# turntable.net
KiCad netlist of a schematic drawn in EAGLE
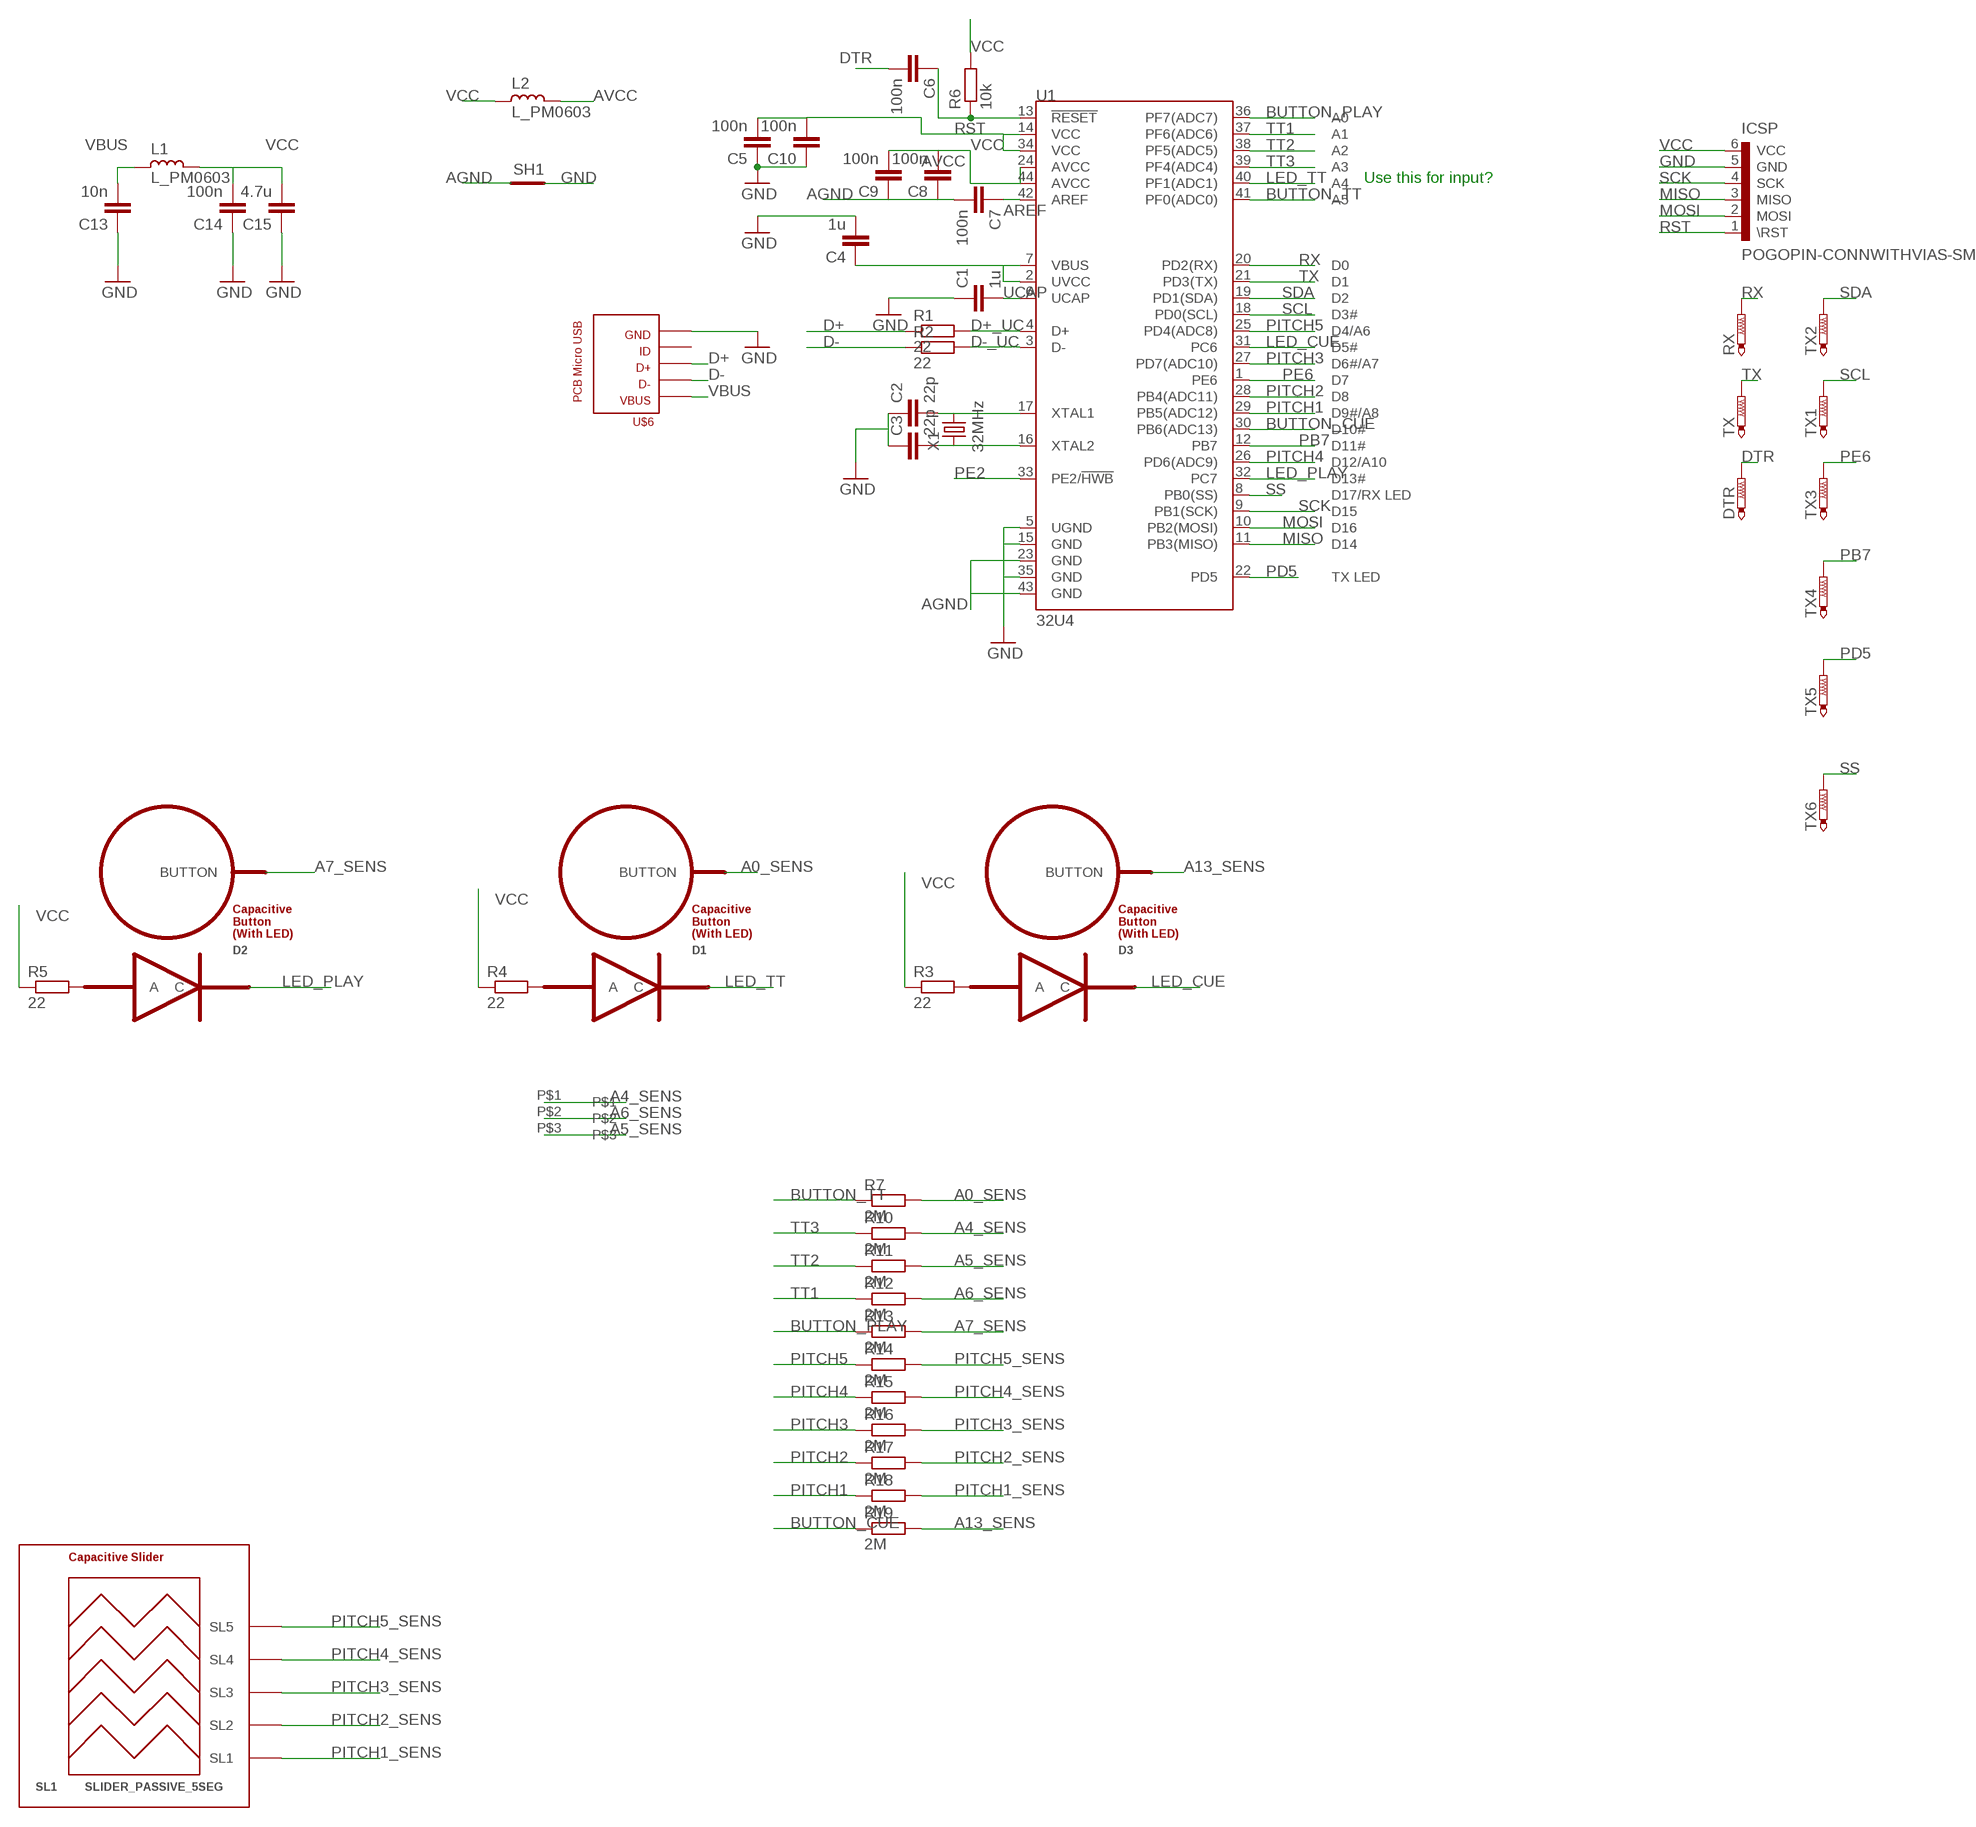
[diagram p0: schematic, sheet 1]

(export (version "E")
  (design (tool "Eeschema 10.0.6"))
  (components
    (comp (ref "C1")
      (value "1u")
      (footprint "eagle-import:C0402")
      (libsource (lib "eagle-import") (part "C-EUC0402"))
    )
    (comp (ref "C2")
      (value "22p")
      (footprint "eagle-import:C0402")
      (libsource (lib "eagle-import") (part "C-EUC0402"))
    )
    (comp (ref "C3")
      (value "22p")
      (footprint "eagle-import:C0402")
      (libsource (lib "eagle-import") (part "C-EUC0402"))
    )
    (comp (ref "C4")
      (value "1u")
      (footprint "eagle-import:C0402")
      (libsource (lib "eagle-import") (part "C-EUC0402"))
    )
    (comp (ref "C5")
      (value "100n")
      (footprint "eagle-import:C0402")
      (libsource (lib "eagle-import") (part "C-EUC0402"))
    )
    (comp (ref "C6")
      (value "100n")
      (footprint "eagle-import:C0402")
      (libsource (lib "eagle-import") (part "C-EUC0402"))
    )
    (comp (ref "C7")
      (value "100n")
      (footprint "eagle-import:C0402")
      (libsource (lib "eagle-import") (part "C-EUC0402"))
    )
    (comp (ref "C8")
      (value "100n")
      (footprint "eagle-import:C0402")
      (libsource (lib "eagle-import") (part "C-EUC0402"))
    )
    (comp (ref "C9")
      (value "100n")
      (footprint "eagle-import:C0402")
      (libsource (lib "eagle-import") (part "C-EUC0402"))
    )
    (comp (ref "C10")
      (value "100n")
      (footprint "eagle-import:C0402")
      (libsource (lib "eagle-import") (part "C-EUC0402"))
    )
    (comp (ref "C13")
      (value "10n")
      (footprint "eagle-import:C0402")
      (libsource (lib "eagle-import") (part "C-EUC0402"))
    )
    (comp (ref "C14")
      (value "100n")
      (footprint "eagle-import:C0402")
      (libsource (lib "eagle-import") (part "C-EUC0402"))
    )
    (comp (ref "C15")
      (value "4.7u")
      (footprint "eagle-import:C0402")
      (libsource (lib "eagle-import") (part "C-EUC0402"))
    )
    (comp (ref "D1")
      (value "LED_BUTTON")
      (footprint "eagle-import:LED_BUTTON")
      (libsource (lib "eagle-import") (part "LED_BUTTON"))
    )
    (comp (ref "D2")
      (value "LED_BUTTON")
      (footprint "eagle-import:LED_BUTTON")
      (libsource (lib "eagle-import") (part "LED_BUTTON"))
    )
    (comp (ref "D3")
      (value "LED_BUTTON")
      (footprint "eagle-import:LED_BUTTON")
      (libsource (lib "eagle-import") (part "LED_BUTTON"))
    )
    (comp (ref "DTR")
      (value "PTR1TP06R")
      (footprint "eagle-import:TP06R")
      (libsource (lib "eagle-import") (part "PTR1TP06R"))
    )
    (comp (ref "ICSP")
      (value "POGOPIN-CONNWITHVIAS-SMV")
      (footprint "eagle-import:POGOPROG-CONN-OH-SMALLERVIAS")
      (libsource (lib "eagle-import") (part "POGOPIN-CONNWITHVIAS-SMV"))
    )
    (comp (ref "L1")
      (value "L_PM0603")
      (footprint "eagle-import:PM0603")
      (libsource (lib "eagle-import") (part "L_PM0603"))
    )
    (comp (ref "L2")
      (value "L_PM0603")
      (footprint "eagle-import:PM0603")
      (libsource (lib "eagle-import") (part "L_PM0603"))
    )
    (comp (ref "R1")
      (value "22")
      (footprint "eagle-import:R0402")
      (libsource (lib "eagle-import") (part "R-EU_R0402"))
    )
    (comp (ref "R2")
      (value "22")
      (footprint "eagle-import:R0402")
      (libsource (lib "eagle-import") (part "R-EU_R0402"))
    )
    (comp (ref "R3")
      (value "22")
      (footprint "eagle-import:R0402")
      (libsource (lib "eagle-import") (part "R-EU_R0402"))
    )
    (comp (ref "R4")
      (value "22")
      (footprint "eagle-import:R0402")
      (libsource (lib "eagle-import") (part "R-EU_R0402"))
    )
    (comp (ref "R5")
      (value "22")
      (footprint "eagle-import:R0402")
      (libsource (lib "eagle-import") (part "R-EU_R0402"))
    )
    (comp (ref "R6")
      (value "10k")
      (footprint "eagle-import:R0402")
      (libsource (lib "eagle-import") (part "R-EU_R0402"))
    )
    (comp (ref "R7")
      (value "2M")
      (footprint "eagle-import:R0402")
      (libsource (lib "eagle-import") (part "R-EU_R0402"))
    )
    (comp (ref "R10")
      (value "2M")
      (footprint "eagle-import:R0402")
      (libsource (lib "eagle-import") (part "R-EU_R0402"))
    )
    (comp (ref "R11")
      (value "2M")
      (footprint "eagle-import:R0402")
      (libsource (lib "eagle-import") (part "R-EU_R0402"))
    )
    (comp (ref "R12")
      (value "2M")
      (footprint "eagle-import:R0402")
      (libsource (lib "eagle-import") (part "R-EU_R0402"))
    )
    (comp (ref "R13")
      (value "2M")
      (footprint "eagle-import:R0402")
      (libsource (lib "eagle-import") (part "R-EU_R0402"))
    )
    (comp (ref "R14")
      (value "2M")
      (footprint "eagle-import:R0402")
      (libsource (lib "eagle-import") (part "R-EU_R0402"))
    )
    (comp (ref "R15")
      (value "2M")
      (footprint "eagle-import:R0402")
      (libsource (lib "eagle-import") (part "R-EU_R0402"))
    )
    (comp (ref "R16")
      (value "2M")
      (footprint "eagle-import:R0402")
      (libsource (lib "eagle-import") (part "R-EU_R0402"))
    )
    (comp (ref "R17")
      (value "2M")
      (footprint "eagle-import:R0402")
      (libsource (lib "eagle-import") (part "R-EU_R0402"))
    )
    (comp (ref "R18")
      (value "2M")
      (footprint "eagle-import:R0402")
      (libsource (lib "eagle-import") (part "R-EU_R0402"))
    )
    (comp (ref "R19")
      (value "2M")
      (footprint "eagle-import:R0402")
      (libsource (lib "eagle-import") (part "R-EU_R0402"))
    )
    (comp (ref "RX")
      (value "PTR1TP06R")
      (footprint "eagle-import:TP06R")
      (libsource (lib "eagle-import") (part "PTR1TP06R"))
    )
    (comp (ref "SH1")
      (value "SHORT")
      (footprint "eagle-import:SHORT_TOP-6")
      (libsource (lib "eagle-import") (part "SHORT"))
    )
    (comp (ref "SL1")
      (value "SLIDER_PASSIVE_5SEG")
      (footprint "eagle-import:SLIDER_PASSIVE_5SEG_12MM")
      (libsource (lib "eagle-import") (part "SLIDER_PASSIVE_5SEG"))
    )
    (comp (ref "TX")
      (value "PTR1TP06R")
      (footprint "eagle-import:TP06R")
      (libsource (lib "eagle-import") (part "PTR1TP06R"))
    )
    (comp (ref "TX1")
      (value "PTR1TP06R")
      (footprint "eagle-import:TP06R")
      (libsource (lib "eagle-import") (part "PTR1TP06R"))
    )
    (comp (ref "TX2")
      (value "PTR1TP06R")
      (footprint "eagle-import:TP06R")
      (libsource (lib "eagle-import") (part "PTR1TP06R"))
    )
    (comp (ref "TX3")
      (value "PTR1TP06R")
      (footprint "eagle-import:TP06R")
      (libsource (lib "eagle-import") (part "PTR1TP06R"))
    )
    (comp (ref "TX4")
      (value "PTR1TP06R")
      (footprint "eagle-import:TP06R")
      (libsource (lib "eagle-import") (part "PTR1TP06R"))
    )
    (comp (ref "TX5")
      (value "PTR1TP06R")
      (footprint "eagle-import:TP06R")
      (libsource (lib "eagle-import") (part "PTR1TP06R"))
    )
    (comp (ref "TX6")
      (value "PTR1TP06R")
      (footprint "eagle-import:TP06R")
      (libsource (lib "eagle-import") (part "PTR1TP06R"))
    )
    (comp (ref "U$1")
      (value "TURNTABLE")
      (footprint "eagle-import:TURNTABLE")
      (libsource (lib "eagle-import") (part "TURNTABLE"))
    )
    (comp (ref "U$6")
      (value "PCB_MICRO_USB_BSS_2")
      (footprint "eagle-import:USB_TYPE_B_SS_2")
      (libsource (lib "eagle-import") (part "PCB_MICRO_USB_BSS_2"))
    )
    (comp (ref "U1")
      (value "32U4")
      (footprint "eagle-import:QFN-44")
      (libsource (lib "eagle-import") (part "ATMEGA32U4QFN"))
    )
    (comp (ref "X1")
      (value "32MHz")
      (footprint "eagle-import:CRYSTAL-SMD-2.0X1.6MM")
      (libsource (lib "eagle-import") (part "CRYSTAL-32MHZ-SMD-2.0X1.6MM"))
    )
  )
  (nets
    (net (code "1") (name "/A0_SENS") (class "Default")
      (node (ref "D1") (pin "BUTTON") (pinfunction "BUTTON_BUTTON") (pintype "passive"))
      (node (ref "R7") (pin "2") (pinfunction "2_2") (pintype "passive"))
    )
    (net (code "2") (name "/A4_SENS") (class "Default")
      (node (ref "R10") (pin "2") (pinfunction "2_2") (pintype "passive"))
      (node (ref "U$1") (pin "P$1") (pinfunction "P$1_P$1") (pintype "bidirectional"))
    )
    (net (code "3") (name "/A5_SENS") (class "Default")
      (node (ref "R11") (pin "2") (pinfunction "2_2") (pintype "passive"))
      (node (ref "U$1") (pin "P$3") (pinfunction "P$3_P$3") (pintype "bidirectional"))
    )
    (net (code "4") (name "/A6_SENS") (class "Default")
      (node (ref "R12") (pin "2") (pinfunction "2_2") (pintype "passive"))
      (node (ref "U$1") (pin "P$2") (pinfunction "P$2_P$2") (pintype "bidirectional"))
    )
    (net (code "5") (name "/A7_SENS") (class "Default")
      (node (ref "D2") (pin "BUTTON") (pinfunction "BUTTON_BUTTON") (pintype "passive"))
      (node (ref "R13") (pin "2") (pinfunction "2_2") (pintype "passive"))
    )
    (net (code "6") (name "/A13_SENS") (class "Default")
      (node (ref "D3") (pin "BUTTON") (pinfunction "BUTTON_BUTTON") (pintype "passive"))
      (node (ref "R19") (pin "2") (pinfunction "2_2") (pintype "passive"))
    )
    (net (code "7") (name "/AGND") (class "Default")
      (node (ref "C7") (pin "2") (pinfunction "2_2") (pintype "passive"))
      (node (ref "C8") (pin "1") (pinfunction "1_1") (pintype "passive"))
      (node (ref "C9") (pin "1") (pinfunction "1_1") (pintype "passive"))
      (node (ref "SH1") (pin "1") (pinfunction "P$1_1") (pintype "bidirectional"))
      (node (ref "U1") (pin "23") (pinfunction "GND_23") (pintype "bidirectional"))
      (node (ref "U1") (pin "43") (pinfunction "GND_43") (pintype "bidirectional"))
    )
    (net (code "8") (name "/AREF") (class "Default")
      (node (ref "C7") (pin "1") (pinfunction "1_1") (pintype "passive"))
      (node (ref "U1") (pin "42") (pinfunction "AREF_42") (pintype "bidirectional"))
    )
    (net (code "9") (name "/AVCC") (class "Default")
      (node (ref "C8") (pin "2") (pinfunction "2_2") (pintype "passive"))
      (node (ref "C9") (pin "2") (pinfunction "2_2") (pintype "passive"))
      (node (ref "L2") (pin "1") (pinfunction "1_1") (pintype "passive"))
      (node (ref "U1") (pin "24") (pinfunction "AVCC_24") (pintype "bidirectional"))
      (node (ref "U1") (pin "44") (pinfunction "AVCC_44") (pintype "bidirectional"))
    )
    (net (code "10") (name "/BUTTON_CUE") (class "Default")
      (node (ref "R19") (pin "1") (pinfunction "1_1") (pintype "passive"))
      (node (ref "U1") (pin "30") (pinfunction "PB6(ADC13)_30") (pintype "bidirectional"))
    )
    (net (code "11") (name "/BUTTON_PLAY") (class "Default")
      (node (ref "R13") (pin "1") (pinfunction "1_1") (pintype "passive"))
      (node (ref "U1") (pin "36") (pinfunction "PF7(ADC7)_36") (pintype "bidirectional"))
    )
    (net (code "12") (name "/BUTTON_TT") (class "Default")
      (node (ref "R7") (pin "1") (pinfunction "1_1") (pintype "passive"))
      (node (ref "U1") (pin "41") (pinfunction "PF0(ADC0)_41") (pintype "bidirectional"))
    )
    (net (code "13") (name "/D+") (class "Default")
      (node (ref "R1") (pin "1") (pinfunction "1_1") (pintype "passive"))
      (node (ref "U$6") (pin "3") (pinfunction "3_3") (pintype "bidirectional"))
    )
    (net (code "14") (name "/D+_UC") (class "Default")
      (node (ref "R1") (pin "2") (pinfunction "2_2") (pintype "passive"))
      (node (ref "U1") (pin "4") (pinfunction "D+_4") (pintype "bidirectional"))
    )
    (net (code "15") (name "/D-") (class "Default")
      (node (ref "R2") (pin "1") (pinfunction "1_1") (pintype "passive"))
      (node (ref "U$6") (pin "2") (pinfunction "2_2") (pintype "bidirectional"))
    )
    (net (code "16") (name "/D-_UC") (class "Default")
      (node (ref "R2") (pin "2") (pinfunction "2_2") (pintype "passive"))
      (node (ref "U1") (pin "3") (pinfunction "D-_3") (pintype "bidirectional"))
    )
    (net (code "17") (name "/DTR") (class "Default")
      (node (ref "C6") (pin "2") (pinfunction "2_2") (pintype "passive"))
      (node (ref "DTR") (pin "TP") (pinfunction "TP_TP") (pintype "input"))
    )
    (net (code "18") (name "/LED_CUE") (class "Default")
      (node (ref "D3") (pin "C") (pinfunction "C_C") (pintype "bidirectional"))
      (node (ref "U1") (pin "31") (pinfunction "PC6_31") (pintype "bidirectional"))
    )
    (net (code "19") (name "/LED_PLAY") (class "Default")
      (node (ref "D2") (pin "C") (pinfunction "C_C") (pintype "bidirectional"))
      (node (ref "U1") (pin "32") (pinfunction "PC7_32") (pintype "bidirectional"))
    )
    (net (code "20") (name "/LED_TT") (class "Default")
      (node (ref "D1") (pin "C") (pinfunction "C_C") (pintype "bidirectional"))
      (node (ref "U1") (pin "40") (pinfunction "PF1(ADC1)_40") (pintype "bidirectional"))
    )
    (net (code "21") (name "/MISO") (class "Default")
      (node (ref "ICSP") (pin "3") (pinfunction "MISO_3") (pintype "bidirectional"))
      (node (ref "U1") (pin "11") (pinfunction "PB3(MISO)_11") (pintype "bidirectional"))
    )
    (net (code "22") (name "/MOSI") (class "Default")
      (node (ref "ICSP") (pin "2") (pinfunction "MOSI_2") (pintype "bidirectional"))
      (node (ref "U1") (pin "10") (pinfunction "PB2(MOSI)_10") (pintype "bidirectional"))
    )
    (net (code "23") (name "/PB7") (class "Default")
      (node (ref "TX4") (pin "TP") (pinfunction "TP_TP") (pintype "input"))
      (node (ref "U1") (pin "12") (pinfunction "PB7_12") (pintype "bidirectional"))
    )
    (net (code "24") (name "/PD5") (class "Default")
      (node (ref "TX5") (pin "TP") (pinfunction "TP_TP") (pintype "input"))
      (node (ref "U1") (pin "22") (pinfunction "PD5_22") (pintype "bidirectional"))
    )
    (net (code "25") (name "/PE2") (class "Default")
      (node (ref "U1") (pin "33") (pinfunction "PE2/~{HWB}_33") (pintype "bidirectional"))
    )
    (net (code "26") (name "/PE6") (class "Default")
      (node (ref "TX3") (pin "TP") (pinfunction "TP_TP") (pintype "input"))
      (node (ref "U1") (pin "1") (pinfunction "PE6_1") (pintype "bidirectional"))
    )
    (net (code "27") (name "/PITCH1") (class "Default")
      (node (ref "R18") (pin "1") (pinfunction "1_1") (pintype "passive"))
      (node (ref "U1") (pin "29") (pinfunction "PB5(ADC12)_29") (pintype "bidirectional"))
    )
    (net (code "28") (name "/PITCH1_SENS") (class "Default")
      (node (ref "R18") (pin "2") (pinfunction "2_2") (pintype "passive"))
      (node (ref "SL1") (pin "SL1") (pinfunction "SL1_SL1") (pintype "passive"))
    )
    (net (code "29") (name "/PITCH2") (class "Default")
      (node (ref "R17") (pin "1") (pinfunction "1_1") (pintype "passive"))
      (node (ref "U1") (pin "28") (pinfunction "PB4(ADC11)_28") (pintype "bidirectional"))
    )
    (net (code "30") (name "/PITCH2_SENS") (class "Default")
      (node (ref "R17") (pin "2") (pinfunction "2_2") (pintype "passive"))
      (node (ref "SL1") (pin "SL2") (pinfunction "SL2_SL2") (pintype "passive"))
    )
    (net (code "31") (name "/PITCH3") (class "Default")
      (node (ref "R16") (pin "1") (pinfunction "1_1") (pintype "passive"))
      (node (ref "U1") (pin "27") (pinfunction "PD7(ADC10)_27") (pintype "bidirectional"))
    )
    (net (code "32") (name "/PITCH3_SENS") (class "Default")
      (node (ref "R16") (pin "2") (pinfunction "2_2") (pintype "passive"))
      (node (ref "SL1") (pin "SL3") (pinfunction "SL3_SL3") (pintype "passive"))
    )
    (net (code "33") (name "/PITCH4") (class "Default")
      (node (ref "R15") (pin "1") (pinfunction "1_1") (pintype "passive"))
      (node (ref "U1") (pin "26") (pinfunction "PD6(ADC9)_26") (pintype "bidirectional"))
    )
    (net (code "34") (name "/PITCH4_SENS") (class "Default")
      (node (ref "R15") (pin "2") (pinfunction "2_2") (pintype "passive"))
      (node (ref "SL1") (pin "SL4") (pinfunction "SL4_SL4") (pintype "passive"))
    )
    (net (code "35") (name "/PITCH5") (class "Default")
      (node (ref "R14") (pin "1") (pinfunction "1_1") (pintype "passive"))
      (node (ref "U1") (pin "25") (pinfunction "PD4(ADC8)_25") (pintype "bidirectional"))
    )
    (net (code "36") (name "/PITCH5_SENS") (class "Default")
      (node (ref "R14") (pin "2") (pinfunction "2_2") (pintype "passive"))
      (node (ref "SL1") (pin "SL5") (pinfunction "SL5_SL5") (pintype "passive"))
    )
    (net (code "37") (name "/RST") (class "Default")
      (node (ref "C6") (pin "1") (pinfunction "1_1") (pintype "passive"))
      (node (ref "ICSP") (pin "1") (pinfunction "\\RST_1") (pintype "bidirectional"))
      (node (ref "R6") (pin "1") (pinfunction "1_1") (pintype "passive"))
      (node (ref "U1") (pin "13") (pinfunction "~{RESET}_13") (pintype "bidirectional"))
    )
    (net (code "38") (name "/RX") (class "Default")
      (node (ref "RX") (pin "TP") (pinfunction "TP_TP") (pintype "input"))
      (node (ref "U1") (pin "20") (pinfunction "PD2(RX)_20") (pintype "bidirectional"))
    )
    (net (code "39") (name "/SCK") (class "Default")
      (node (ref "ICSP") (pin "4") (pinfunction "SCK_4") (pintype "bidirectional"))
      (node (ref "U1") (pin "9") (pinfunction "PB1(SCK)_9") (pintype "bidirectional"))
    )
    (net (code "40") (name "/SCL") (class "Default")
      (node (ref "TX1") (pin "TP") (pinfunction "TP_TP") (pintype "input"))
      (node (ref "U1") (pin "18") (pinfunction "PD0(SCL)_18") (pintype "bidirectional"))
    )
    (net (code "41") (name "/SDA") (class "Default")
      (node (ref "TX2") (pin "TP") (pinfunction "TP_TP") (pintype "input"))
      (node (ref "U1") (pin "19") (pinfunction "PD1(SDA)_19") (pintype "bidirectional"))
    )
    (net (code "42") (name "/SS") (class "Default")
      (node (ref "TX6") (pin "TP") (pinfunction "TP_TP") (pintype "input"))
      (node (ref "U1") (pin "8") (pinfunction "PB0(SS)_8") (pintype "bidirectional"))
    )
    (net (code "43") (name "/TT1") (class "Default")
      (node (ref "R12") (pin "1") (pinfunction "1_1") (pintype "passive"))
      (node (ref "U1") (pin "37") (pinfunction "PF6(ADC6)_37") (pintype "bidirectional"))
    )
    (net (code "44") (name "/TT2") (class "Default")
      (node (ref "R11") (pin "1") (pinfunction "1_1") (pintype "passive"))
      (node (ref "U1") (pin "38") (pinfunction "PF5(ADC5)_38") (pintype "bidirectional"))
    )
    (net (code "45") (name "/TT3") (class "Default")
      (node (ref "R10") (pin "1") (pinfunction "1_1") (pintype "passive"))
      (node (ref "U1") (pin "39") (pinfunction "PF4(ADC4)_39") (pintype "bidirectional"))
    )
    (net (code "46") (name "/TX") (class "Default")
      (node (ref "TX") (pin "TP") (pinfunction "TP_TP") (pintype "input"))
      (node (ref "U1") (pin "21") (pinfunction "PD3(TX)_21") (pintype "bidirectional"))
    )
    (net (code "47") (name "/UCAP") (class "Default")
      (node (ref "C1") (pin "2") (pinfunction "2_2") (pintype "passive"))
      (node (ref "U1") (pin "6") (pinfunction "UCAP_6") (pintype "bidirectional"))
    )
    (net (code "48") (name "/VBUS") (class "Default")
      (node (ref "C13") (pin "2") (pinfunction "2_2") (pintype "passive"))
      (node (ref "L1") (pin "2") (pinfunction "2_2") (pintype "passive"))
      (node (ref "U$6") (pin "1") (pinfunction "1_1") (pintype "bidirectional"))
    )
    (net (code "49") (name "/VCC") (class "Default")
      (node (ref "C10") (pin "2") (pinfunction "2_2") (pintype "passive"))
      (node (ref "C14") (pin "2") (pinfunction "2_2") (pintype "passive"))
      (node (ref "C15") (pin "2") (pinfunction "2_2") (pintype "passive"))
      (node (ref "C4") (pin "1") (pinfunction "1_1") (pintype "passive"))
      (node (ref "C5") (pin "2") (pinfunction "2_2") (pintype "passive"))
      (node (ref "ICSP") (pin "6") (pinfunction "VCC_6") (pintype "bidirectional"))
      (node (ref "L1") (pin "1") (pinfunction "1_1") (pintype "passive"))
      (node (ref "L2") (pin "2") (pinfunction "2_2") (pintype "passive"))
      (node (ref "R3") (pin "1") (pinfunction "1_1") (pintype "passive"))
      (node (ref "R4") (pin "1") (pinfunction "1_1") (pintype "passive"))
      (node (ref "R5") (pin "1") (pinfunction "1_1") (pintype "passive"))
      (node (ref "R6") (pin "2") (pinfunction "2_2") (pintype "passive"))
      (node (ref "U1") (pin "14") (pinfunction "VCC_14") (pintype "bidirectional"))
      (node (ref "U1") (pin "2") (pinfunction "UVCC_2") (pintype "bidirectional"))
      (node (ref "U1") (pin "34") (pinfunction "VCC_34") (pintype "bidirectional"))
      (node (ref "U1") (pin "7") (pinfunction "VBUS_7") (pintype "bidirectional"))
    )
    (net (code "50") (name "GND") (class "Default")
      (node (ref "C1") (pin "1") (pinfunction "1_1") (pintype "passive"))
      (node (ref "C10") (pin "1") (pinfunction "1_1") (pintype "passive"))
      (node (ref "C13") (pin "1") (pinfunction "1_1") (pintype "passive"))
      (node (ref "C14") (pin "1") (pinfunction "1_1") (pintype "passive"))
      (node (ref "C15") (pin "1") (pinfunction "1_1") (pintype "passive"))
      (node (ref "C2") (pin "1") (pinfunction "1_1") (pintype "passive"))
      (node (ref "C3") (pin "1") (pinfunction "1_1") (pintype "passive"))
      (node (ref "C4") (pin "2") (pinfunction "2_2") (pintype "passive"))
      (node (ref "C5") (pin "1") (pinfunction "1_1") (pintype "passive"))
      (node (ref "ICSP") (pin "5") (pinfunction "GND_5") (pintype "bidirectional"))
      (node (ref "SH1") (pin "2") (pinfunction "P$2_2") (pintype "bidirectional"))
      (node (ref "U$6") (pin "5") (pinfunction "5_5") (pintype "bidirectional"))
      (node (ref "U1") (pin "15") (pinfunction "GND_15") (pintype "bidirectional"))
      (node (ref "U1") (pin "35") (pinfunction "GND_35") (pintype "bidirectional"))
      (node (ref "U1") (pin "5") (pinfunction "UGND_5") (pintype "bidirectional"))
    )
    (net (code "51") (name "Net-(D1-PadA)") (class "Default")
      (node (ref "D1") (pin "A") (pinfunction "A_A") (pintype "bidirectional"))
      (node (ref "R4") (pin "2") (pinfunction "2_2") (pintype "passive"))
    )
    (net (code "52") (name "Net-(D2-PadA)") (class "Default")
      (node (ref "D2") (pin "A") (pinfunction "A_A") (pintype "bidirectional"))
      (node (ref "R5") (pin "2") (pinfunction "2_2") (pintype "passive"))
    )
    (net (code "53") (name "Net-(D3-PadA)") (class "Default")
      (node (ref "D3") (pin "A") (pinfunction "A_A") (pintype "bidirectional"))
      (node (ref "R3") (pin "2") (pinfunction "2_2") (pintype "passive"))
    )
    (net (code "54") (name "Net-(U1-XTAL1)") (class "Default")
      (node (ref "C2") (pin "2") (pinfunction "2_2") (pintype "passive"))
      (node (ref "U1") (pin "17") (pinfunction "XTAL1_17") (pintype "bidirectional"))
      (node (ref "X1") (pin "3") (pinfunction "2_3") (pintype "passive"))
    )
    (net (code "55") (name "Net-(U1-XTAL2)") (class "Default")
      (node (ref "C3") (pin "2") (pinfunction "2_2") (pintype "passive"))
      (node (ref "U1") (pin "16") (pinfunction "XTAL2_16") (pintype "bidirectional"))
      (node (ref "X1") (pin "1") (pinfunction "1_1") (pintype "passive"))
    )
    (net (code "56") (name "unconnected-(U$6-Pad4)") (class "Default")
      (node (ref "U$6") (pin "4") (pinfunction "4_4") (pintype "bidirectional"))
    )
  )
)
